# SR_latch_Schematic.net
KiCad netlist of a schematic drawn in Altium Designer
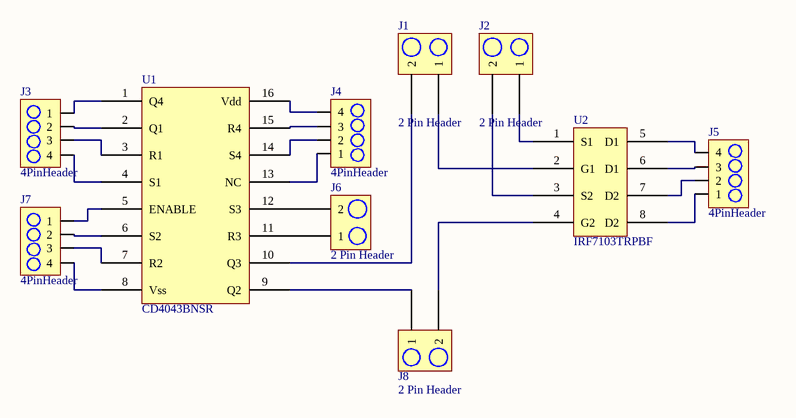
[diagram p0: SR latch Schematic.SchDoc]

(export (version "E")
  (design (tool "Eeschema 10.0.6"))
  (components
    (comp (ref "J1")
      (value "2 Pin Header")
      (footprint "2PIN_HEADER")
      (description "2 pin connector")
      (libsource (lib "SchlibforSRlatchFootprint") (part "2 Pin Header"))
    )
    (comp (ref "J2")
      (value "2 Pin Header")
      (footprint "2PIN_HEADER")
      (description "2 pin connector")
      (libsource (lib "SchlibforSRlatchFootprint") (part "2 Pin Header"))
    )
    (comp (ref "J3")
      (value "4PinHeader")
      (footprint "4PIN_HEADER")
      (libsource (lib "SchlibforSRlatchFootprint") (part "4PinHeader"))
    )
    (comp (ref "J4")
      (value "4PinHeader")
      (footprint "4PIN_HEADER")
      (libsource (lib "") (part "4PinHeader_1"))
    )
    (comp (ref "J5")
      (value "4PinHeader")
      (footprint "4PIN_HEADER")
      (libsource (lib "") (part "4PinHeader_1"))
    )
    (comp (ref "J6")
      (value "2 Pin Header")
      (footprint "2PIN_HEADER")
      (description "2 pin connector")
      (libsource (lib "") (part "2 Pin Header_1"))
    )
    (comp (ref "J7")
      (value "4PinHeader")
      (footprint "4PIN_HEADER")
      (libsource (lib "SchlibforSRlatchFootprint") (part "4PinHeader"))
    )
    (comp (ref "J8")
      (value "2 Pin Header")
      (footprint "2PIN_HEADER")
      (description "2 pin connector")
      (libsource (lib "") (part "2 Pin Header_2"))
    )
    (comp (ref "U1")
      (value "CD4043BNSR")
      (footprint "SOIC-16SRLATCH")
      (description "IC NOR R/S LATCH 3ST QUAD 16SO")
      (fields
        (field (name "MANUFACTURER") "Texas Instruments")
        (field (name "MANUFACTURER PART NUMBER") "CD4043BNSRE4")
      )
      (libsource (lib "SchlibforSRlatchFootprint") (part "CD4043BNSR"))
    )
    (comp (ref "U2")
      (value "IRF7103TRPBF")
      (footprint "SOIC127P600X175-8N")
      (description "MOSFET 2N-CH 50V 3A 8-SOIC")
      (fields (field (name "MANUFACTURER") "International Rectifier"))
      (libsource (lib "SchlibforSRlatchFootprint") (part "IRF7103TRPBF"))
    )
  )
  (nets
    (net (code "1") (name "Net-(J5-Pad1)") (class "Default")
      (node (ref "J5") (pin "1") (pinfunction "1_1") (pintype "passive"))
      (node (ref "U2") (pin "8") (pinfunction "D2_8") (pintype "passive"))
    )
    (net (code "2") (name "Net-(J5-Pad2)") (class "Default")
      (node (ref "J5") (pin "2") (pinfunction "2_2") (pintype "passive"))
      (node (ref "U2") (pin "7") (pinfunction "D2_7") (pintype "passive"))
    )
    (net (code "3") (name "Net-(J5-Pad3)") (class "Default")
      (node (ref "J5") (pin "3") (pinfunction "3_3") (pintype "passive"))
      (node (ref "U2") (pin "6") (pinfunction "D1_6") (pintype "passive"))
    )
    (net (code "4") (name "Net-(J5-Pad4)") (class "Default")
      (node (ref "J5") (pin "4") (pinfunction "4_4") (pintype "passive"))
      (node (ref "U2") (pin "5") (pinfunction "D1_5") (pintype "passive"))
    )
    (net (code "5") (name "Net-(U1-ENABLE)") (class "Default")
      (node (ref "J7") (pin "1") (pinfunction "1_1") (pintype "passive"))
      (node (ref "U1") (pin "5") (pinfunction "ENABLE_5") (pintype "passive"))
    )
    (net (code "6") (name "Net-(U1-NC)") (class "Default")
      (node (ref "J4") (pin "1") (pinfunction "1_1") (pintype "passive"))
      (node (ref "U1") (pin "13") (pinfunction "NC_13") (pintype "passive"))
    )
    (net (code "7") (name "Net-(U1-Q1)") (class "Default")
      (node (ref "J3") (pin "2") (pinfunction "2_2") (pintype "passive"))
      (node (ref "U1") (pin "2") (pinfunction "Q1_2") (pintype "passive"))
    )
    (net (code "8") (name "Net-(U1-Q2)") (class "Default")
      (node (ref "J8") (pin "1") (pinfunction "1_1") (pintype "passive"))
      (node (ref "U1") (pin "9") (pinfunction "Q2_9") (pintype "passive"))
    )
    (net (code "9") (name "Net-(U1-Q3)") (class "Default")
      (node (ref "J1") (pin "2") (pinfunction "2_2") (pintype "passive"))
      (node (ref "U1") (pin "10") (pinfunction "Q3_10") (pintype "passive"))
    )
    (net (code "10") (name "Net-(U1-Q4)") (class "Default")
      (node (ref "J3") (pin "1") (pinfunction "1_1") (pintype "passive"))
      (node (ref "U1") (pin "1") (pinfunction "Q4_1") (pintype "passive"))
    )
    (net (code "11") (name "Net-(U1-R1)") (class "Default")
      (node (ref "J3") (pin "3") (pinfunction "3_3") (pintype "passive"))
      (node (ref "U1") (pin "3") (pinfunction "R1_3") (pintype "passive"))
    )
    (net (code "12") (name "Net-(U1-R2)") (class "Default")
      (node (ref "J7") (pin "3") (pinfunction "3_3") (pintype "passive"))
      (node (ref "U1") (pin "7") (pinfunction "R2_7") (pintype "passive"))
    )
    (net (code "13") (name "Net-(U1-R3)") (class "Default")
      (node (ref "J6") (pin "1") (pinfunction "1_1") (pintype "passive"))
      (node (ref "U1") (pin "11") (pinfunction "R3_11") (pintype "passive"))
    )
    (net (code "14") (name "Net-(U1-R4)") (class "Default")
      (node (ref "J4") (pin "3") (pinfunction "3_3") (pintype "passive"))
      (node (ref "U1") (pin "15") (pinfunction "R4_15") (pintype "passive"))
    )
    (net (code "15") (name "Net-(U1-S1)") (class "Default")
      (node (ref "J3") (pin "4") (pinfunction "4_4") (pintype "passive"))
      (node (ref "U1") (pin "4") (pinfunction "S1_4") (pintype "passive"))
    )
    (net (code "16") (name "Net-(U1-S2)") (class "Default")
      (node (ref "J7") (pin "2") (pinfunction "2_2") (pintype "passive"))
      (node (ref "U1") (pin "6") (pinfunction "S2_6") (pintype "passive"))
    )
    (net (code "17") (name "Net-(U1-S3)") (class "Default")
      (node (ref "J6") (pin "2") (pinfunction "2_2") (pintype "passive"))
      (node (ref "U1") (pin "12") (pinfunction "S3_12") (pintype "passive"))
    )
    (net (code "18") (name "Net-(U1-S4)") (class "Default")
      (node (ref "J4") (pin "2") (pinfunction "2_2") (pintype "passive"))
      (node (ref "U1") (pin "14") (pinfunction "S4_14") (pintype "passive"))
    )
    (net (code "19") (name "Net-(U1-Vdd)") (class "Default")
      (node (ref "J4") (pin "4") (pinfunction "4_4") (pintype "passive"))
      (node (ref "U1") (pin "16") (pinfunction "Vdd_16") (pintype "passive"))
    )
    (net (code "20") (name "Net-(U1-Vss)") (class "Default")
      (node (ref "J7") (pin "4") (pinfunction "4_4") (pintype "passive"))
      (node (ref "U1") (pin "8") (pinfunction "Vss_8") (pintype "passive"))
    )
    (net (code "21") (name "Net-(U2-G1)") (class "Default")
      (node (ref "J1") (pin "1") (pinfunction "1_1") (pintype "passive"))
      (node (ref "U2") (pin "2") (pinfunction "G1_2") (pintype "passive"))
    )
    (net (code "22") (name "Net-(U2-G2)") (class "Default")
      (node (ref "J8") (pin "2") (pinfunction "2_2") (pintype "passive"))
      (node (ref "U2") (pin "4") (pinfunction "G2_4") (pintype "passive"))
    )
    (net (code "23") (name "Net-(U2-S1)") (class "Default")
      (node (ref "J2") (pin "1") (pinfunction "1_1") (pintype "passive"))
      (node (ref "U2") (pin "1") (pinfunction "S1_1") (pintype "passive"))
    )
    (net (code "24") (name "Net-(U2-S2)") (class "Default")
      (node (ref "J2") (pin "2") (pinfunction "2_2") (pintype "passive"))
      (node (ref "U2") (pin "3") (pinfunction "S2_3") (pintype "passive"))
    )
  )
)
